# KC_BaseBoardSch.net
KiCad netlist of a schematic drawn in Altium Designer
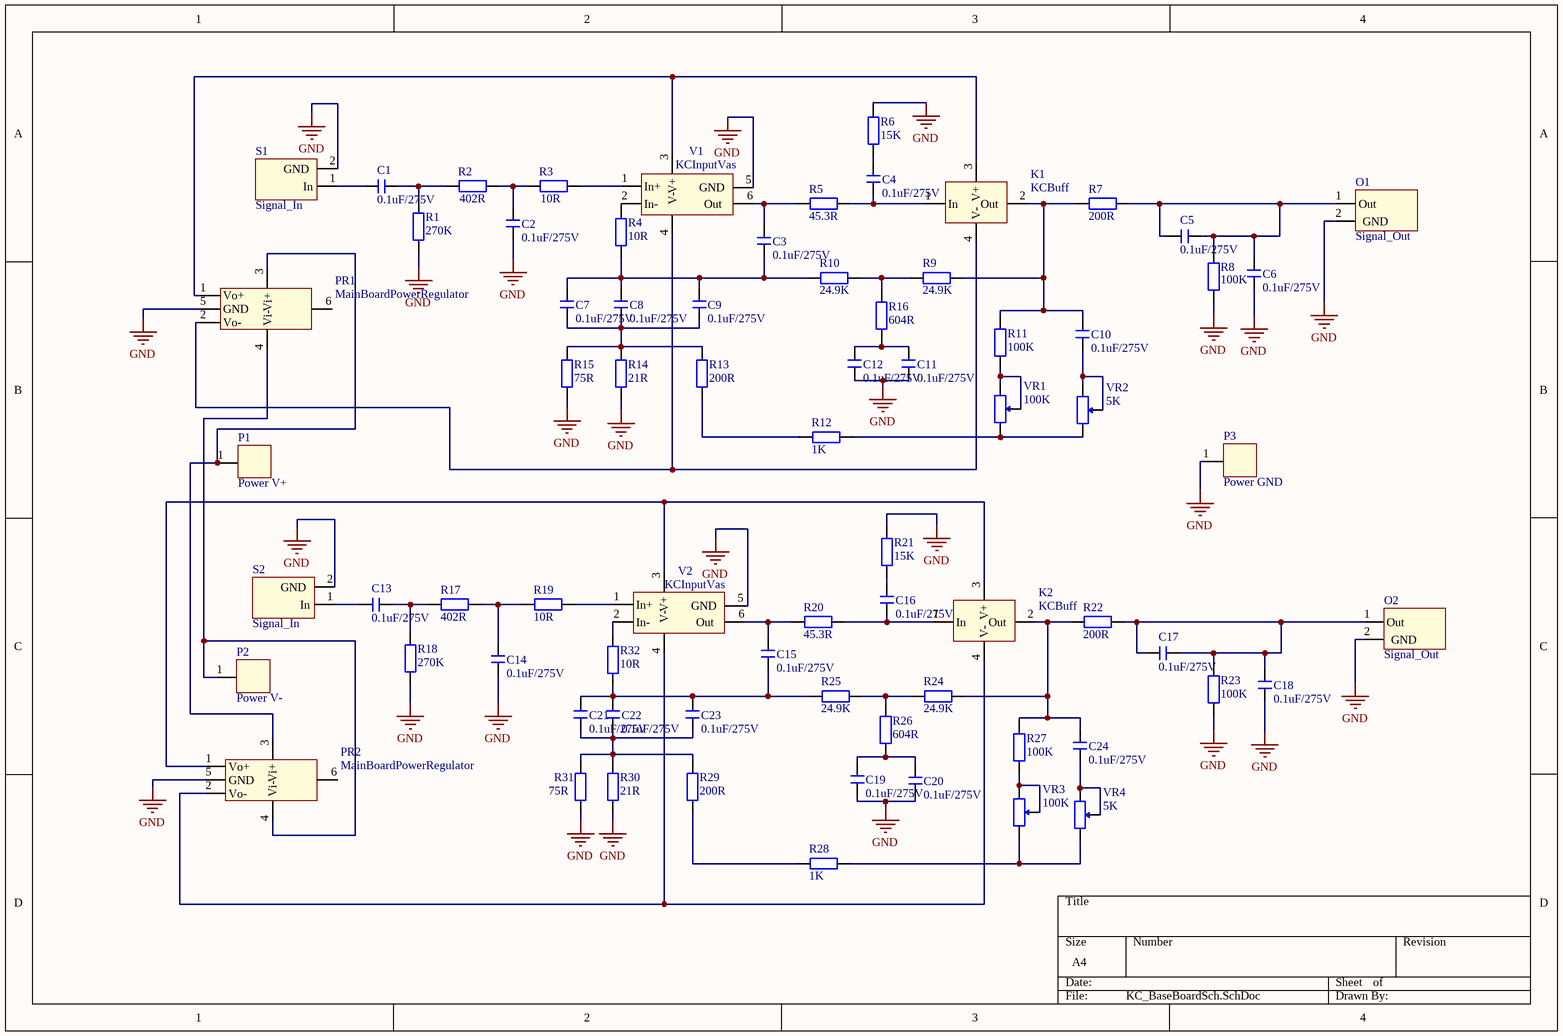
[diagram p0: KC_BaseBoardSch.SchDoc]

(export (version "E")
  (design (tool "Eeschema 10.0.6"))
  (components
    (comp (ref "C1")
      (value "0.1uF/275V")
      (footprint "CBB 50*30*30")
      (description "CBB电容")
      (fields (field (name "版权归属") "源创客"))
      (libsource (lib "电阻-电容-电感") (part "C-CBB"))
    )
    (comp (ref "C2")
      (value "0.1uF/275V")
      (footprint "CBB 6.3*6.3*5")
      (description "CBB电容")
      (fields (field (name "版权归属") "源创客"))
      (libsource (lib "电阻-电容-电感") (part "C-CBB"))
    )
    (comp (ref "C3")
      (value "0.1uF/275V")
      (footprint "CBB 6.3*6.3*5")
      (description "CBB电容")
      (fields (field (name "版权归属") "源创客"))
      (libsource (lib "电阻-电容-电感") (part "C-CBB"))
    )
    (comp (ref "C4")
      (value "0.1uF/275V")
      (footprint "CBB 6.3*6.3*5")
      (description "CBB电容")
      (fields (field (name "版权归属") "源创客"))
      (libsource (lib "电阻-电容-电感") (part "C-CBB"))
    )
    (comp (ref "C5")
      (value "0.1uF/275V")
      (footprint "CBB 6.3*6.3*5")
      (description "CBB电容")
      (fields (field (name "版权归属") "源创客"))
      (libsource (lib "电阻-电容-电感") (part "C-CBB"))
    )
    (comp (ref "C6")
      (value "0.1uF/275V")
      (footprint "CBB 6.3*6.3*5")
      (description "CBB电容")
      (fields (field (name "版权归属") "源创客"))
      (libsource (lib "电阻-电容-电感") (part "C-CBB"))
    )
    (comp (ref "C7")
      (value "0.1uF/275V")
      (footprint "CBB 6.3*6.3*5")
      (description "CBB电容")
      (fields (field (name "版权归属") "源创客"))
      (libsource (lib "电阻-电容-电感") (part "C-CBB"))
    )
    (comp (ref "C8")
      (value "0.1uF/275V")
      (footprint "CBB 6.3*6.3*5")
      (description "CBB电容")
      (fields (field (name "版权归属") "源创客"))
      (libsource (lib "电阻-电容-电感") (part "C-CBB"))
    )
    (comp (ref "C9")
      (value "0.1uF/275V")
      (footprint "CBB 6.3*6.3*5")
      (description "CBB电容")
      (fields (field (name "版权归属") "源创客"))
      (libsource (lib "电阻-电容-电感") (part "C-CBB"))
    )
    (comp (ref "C10")
      (value "0.1uF/275V")
      (footprint "CBB 10*12*8")
      (description "CBB电容")
      (fields (field (name "版权归属") "源创客"))
      (libsource (lib "电阻-电容-电感") (part "C-CBB"))
    )
    (comp (ref "C11")
      (value "0.1uF/275V")
      (footprint "CBB 6.3*6.3*5")
      (description "CBB电容")
      (fields (field (name "版权归属") "源创客"))
      (libsource (lib "电阻-电容-电感") (part "C-CBB"))
    )
    (comp (ref "C12")
      (value "0.1uF/275V")
      (footprint "CBB 6.3*6.3*5")
      (description "CBB电容")
      (fields (field (name "版权归属") "源创客"))
      (libsource (lib "电阻-电容-电感") (part "C-CBB"))
    )
    (comp (ref "C13")
      (value "0.1uF/275V")
      (footprint "CBB 50*30*30")
      (description "CBB电容")
      (fields (field (name "版权归属") "源创客"))
      (libsource (lib "电阻-电容-电感") (part "C-CBB"))
    )
    (comp (ref "C14")
      (value "0.1uF/275V")
      (footprint "CBB 6.3*6.3*5")
      (description "CBB电容")
      (fields (field (name "版权归属") "源创客"))
      (libsource (lib "电阻-电容-电感") (part "C-CBB"))
    )
    (comp (ref "C15")
      (value "0.1uF/275V")
      (footprint "CBB 6.3*6.3*5")
      (description "CBB电容")
      (fields (field (name "版权归属") "源创客"))
      (libsource (lib "电阻-电容-电感") (part "C-CBB"))
    )
    (comp (ref "C16")
      (value "0.1uF/275V")
      (footprint "CBB 6.3*6.3*5")
      (description "CBB电容")
      (fields (field (name "版权归属") "源创客"))
      (libsource (lib "电阻-电容-电感") (part "C-CBB"))
    )
    (comp (ref "C17")
      (value "0.1uF/275V")
      (footprint "CBB 6.3*6.3*5")
      (description "CBB电容")
      (fields (field (name "版权归属") "源创客"))
      (libsource (lib "电阻-电容-电感") (part "C-CBB"))
    )
    (comp (ref "C18")
      (value "0.1uF/275V")
      (footprint "CBB 6.3*6.3*5")
      (description "CBB电容")
      (fields (field (name "版权归属") "源创客"))
      (libsource (lib "电阻-电容-电感") (part "C-CBB"))
    )
    (comp (ref "C19")
      (value "0.1uF/275V")
      (footprint "CBB 6.3*6.3*5")
      (description "CBB电容")
      (fields (field (name "版权归属") "源创客"))
      (libsource (lib "电阻-电容-电感") (part "C-CBB"))
    )
    (comp (ref "C20")
      (value "0.1uF/275V")
      (footprint "CBB 6.3*6.3*5")
      (description "CBB电容")
      (fields (field (name "版权归属") "源创客"))
      (libsource (lib "电阻-电容-电感") (part "C-CBB"))
    )
    (comp (ref "C21")
      (value "0.1uF/275V")
      (footprint "CBB 6.3*6.3*5")
      (description "CBB电容")
      (fields (field (name "版权归属") "源创客"))
      (libsource (lib "电阻-电容-电感") (part "C-CBB"))
    )
    (comp (ref "C22")
      (value "0.1uF/275V")
      (footprint "CBB 6.3*6.3*5")
      (description "CBB电容")
      (fields (field (name "版权归属") "源创客"))
      (libsource (lib "电阻-电容-电感") (part "C-CBB"))
    )
    (comp (ref "C23")
      (value "0.1uF/275V")
      (footprint "CBB 6.3*6.3*5")
      (description "CBB电容")
      (fields (field (name "版权归属") "源创客"))
      (libsource (lib "电阻-电容-电感") (part "C-CBB"))
    )
    (comp (ref "C24")
      (value "0.1uF/275V")
      (footprint "CBB 10*12*8")
      (description "CBB电容")
      (fields (field (name "版权归属") "源创客"))
      (libsource (lib "电阻-电容-电感") (part "C-CBB"))
    )
    (comp (ref "K1")
      (value "KCBuff")
      (footprint "KCBuff")
      (description "King Cello Buffer Stage")
      (libsource (lib "KC_amp") (part "KCBuff"))
    )
    (comp (ref "K2")
      (value "KCBuff")
      (footprint "KCBuff")
      (description "King Cello Buffer Stage")
      (libsource (lib "KC_amp") (part "KCBuff"))
    )
    (comp (ref "O1")
      (value "Signal_Out")
      (footprint "Signal_Terminal")
      (description "Signal Out")
      (libsource (lib "KC_amp") (part "Signal_Out"))
    )
    (comp (ref "O2")
      (value "Signal_Out")
      (footprint "Signal_Terminal")
      (description "Signal Out")
      (libsource (lib "KC_amp") (part "Signal_Out"))
    )
    (comp (ref "P1")
      (value "Power V+")
      (footprint "SinglePin")
      (description "Power Pin")
      (libsource (lib "KC_amp") (part "PowerPin"))
    )
    (comp (ref "P2")
      (value "Power V-")
      (footprint "SinglePin")
      (description "Power Pin")
      (libsource (lib "KC_amp") (part "PowerPin"))
    )
    (comp (ref "P3") (value "Power GND") (footprint "SinglePin") (libsource (lib "KC_amp") (part "PowerPin")))
    (comp (ref "PR1")
      (value "MainBoardPowerRegulator")
      (footprint "KC_MBPowerReg")
      (description "King Cello Main Board Power Regulator")
      (libsource (lib "KC_amp") (part "MainBoardPowerRegulator"))
    )
    (comp (ref "PR2")
      (value "MainBoardPowerRegulator")
      (footprint "KC_MBPowerReg")
      (description "King Cello Main Board Power Regulator")
      (libsource (lib "KC_amp") (part "MainBoardPowerRegulator"))
    )
    (comp (ref "R1")
      (value "270K")
      (footprint "RS 1/2W")
      (description "直插色环电阻")
      (fields (field (name "版权归属") "源创客"))
      (libsource (lib "电阻-电容-电感") (part "R-CRR"))
    )
    (comp (ref "R2")
      (value "402R")
      (footprint "RS 1/2W")
      (description "直插色环电阻")
      (fields (field (name "版权归属") "源创客"))
      (libsource (lib "电阻-电容-电感") (part "R-CRR"))
    )
    (comp (ref "R3")
      (value "10R")
      (footprint "RS 1/2W")
      (description "直插色环电阻")
      (fields (field (name "版权归属") "源创客"))
      (libsource (lib "电阻-电容-电感") (part "R-CRR"))
    )
    (comp (ref "R4")
      (value "10R")
      (footprint "RS 1/2W")
      (description "直插色环电阻")
      (fields (field (name "版权归属") "源创客"))
      (libsource (lib "电阻-电容-电感") (part "R-CRR"))
    )
    (comp (ref "R5")
      (value "45.3R")
      (footprint "RS 1/2W")
      (description "直插色环电阻")
      (fields (field (name "版权归属") "源创客"))
      (libsource (lib "电阻-电容-电感") (part "R-CRR"))
    )
    (comp (ref "R6")
      (value "15K")
      (footprint "RS 1/2W")
      (description "直插色环电阻")
      (fields (field (name "版权归属") "源创客"))
      (libsource (lib "电阻-电容-电感") (part "R-CRR"))
    )
    (comp (ref "R7")
      (value "200R")
      (footprint "RS 1/2W")
      (description "直插色环电阻")
      (fields (field (name "版权归属") "源创客"))
      (libsource (lib "电阻-电容-电感") (part "R-CRR"))
    )
    (comp (ref "R8")
      (value "100K")
      (footprint "RS 1/2W")
      (description "直插色环电阻")
      (fields (field (name "版权归属") "源创客"))
      (libsource (lib "电阻-电容-电感") (part "R-CRR"))
    )
    (comp (ref "R9")
      (value "24.9K")
      (footprint "RS 1/2W")
      (description "直插色环电阻")
      (fields (field (name "版权归属") "源创客"))
      (libsource (lib "电阻-电容-电感") (part "R-CRR"))
    )
    (comp (ref "R10")
      (value "24.9K")
      (footprint "RS 1/2W")
      (description "直插色环电阻")
      (fields (field (name "版权归属") "源创客"))
      (libsource (lib "电阻-电容-电感") (part "R-CRR"))
    )
    (comp (ref "R11")
      (value "100K")
      (footprint "RS 1/2W")
      (description "直插色环电阻")
      (fields (field (name "版权归属") "源创客"))
      (libsource (lib "电阻-电容-电感") (part "R-CRR"))
    )
    (comp (ref "R12")
      (value "1K")
      (footprint "RS 1/2W")
      (description "直插色环电阻")
      (fields (field (name "版权归属") "源创客"))
      (libsource (lib "电阻-电容-电感") (part "R-CRR"))
    )
    (comp (ref "R13")
      (value "200R")
      (footprint "RS 1/2W")
      (description "直插色环电阻")
      (fields (field (name "版权归属") "源创客"))
      (libsource (lib "电阻-电容-电感") (part "R-CRR"))
    )
    (comp (ref "R14")
      (value "21R")
      (footprint "RS 1/2W")
      (description "直插色环电阻")
      (fields (field (name "版权归属") "源创客"))
      (libsource (lib "电阻-电容-电感") (part "R-CRR"))
    )
    (comp (ref "R15")
      (value "75R")
      (footprint "RS 1/2W")
      (description "直插色环电阻")
      (fields (field (name "版权归属") "源创客"))
      (libsource (lib "电阻-电容-电感") (part "R-CRR"))
    )
    (comp (ref "R16")
      (value "604R")
      (footprint "RS 1/2W")
      (description "直插色环电阻")
      (fields (field (name "版权归属") "源创客"))
      (libsource (lib "电阻-电容-电感") (part "R-CRR"))
    )
    (comp (ref "R17")
      (value "402R")
      (footprint "RS 1/2W")
      (description "直插色环电阻")
      (fields (field (name "版权归属") "源创客"))
      (libsource (lib "电阻-电容-电感") (part "R-CRR"))
    )
    (comp (ref "R18")
      (value "270K")
      (footprint "RS 1/2W")
      (description "直插色环电阻")
      (fields (field (name "版权归属") "源创客"))
      (libsource (lib "电阻-电容-电感") (part "R-CRR"))
    )
    (comp (ref "R19")
      (value "10R")
      (footprint "RS 1/2W")
      (description "直插色环电阻")
      (fields (field (name "版权归属") "源创客"))
      (libsource (lib "电阻-电容-电感") (part "R-CRR"))
    )
    (comp (ref "R20")
      (value "45.3R")
      (footprint "RS 1/2W")
      (description "直插色环电阻")
      (fields (field (name "版权归属") "源创客"))
      (libsource (lib "电阻-电容-电感") (part "R-CRR"))
    )
    (comp (ref "R21")
      (value "15K")
      (footprint "RS 1/2W")
      (description "直插色环电阻")
      (fields (field (name "版权归属") "源创客"))
      (libsource (lib "电阻-电容-电感") (part "R-CRR"))
    )
    (comp (ref "R22")
      (value "200R")
      (footprint "RS 1/2W")
      (description "直插色环电阻")
      (fields (field (name "版权归属") "源创客"))
      (libsource (lib "电阻-电容-电感") (part "R-CRR"))
    )
    (comp (ref "R23")
      (value "100K")
      (footprint "RS 1/2W")
      (description "直插色环电阻")
      (fields (field (name "版权归属") "源创客"))
      (libsource (lib "电阻-电容-电感") (part "R-CRR"))
    )
    (comp (ref "R24")
      (value "24.9K")
      (footprint "RS 1/2W")
      (description "直插色环电阻")
      (fields (field (name "版权归属") "源创客"))
      (libsource (lib "电阻-电容-电感") (part "R-CRR"))
    )
    (comp (ref "R25")
      (value "24.9K")
      (footprint "RS 1/2W")
      (description "直插色环电阻")
      (fields (field (name "版权归属") "源创客"))
      (libsource (lib "电阻-电容-电感") (part "R-CRR"))
    )
    (comp (ref "R26")
      (value "604R")
      (footprint "RS 1/2W")
      (description "直插色环电阻")
      (fields (field (name "版权归属") "源创客"))
      (libsource (lib "电阻-电容-电感") (part "R-CRR"))
    )
    (comp (ref "R27")
      (value "100K")
      (footprint "RS 1/2W")
      (description "直插色环电阻")
      (fields (field (name "版权归属") "源创客"))
      (libsource (lib "电阻-电容-电感") (part "R-CRR"))
    )
    (comp (ref "R28")
      (value "1K")
      (footprint "RS 1/2W")
      (description "直插色环电阻")
      (fields (field (name "版权归属") "源创客"))
      (libsource (lib "电阻-电容-电感") (part "R-CRR"))
    )
    (comp (ref "R29")
      (value "200R")
      (footprint "RS 1/2W")
      (description "直插色环电阻")
      (fields (field (name "版权归属") "源创客"))
      (libsource (lib "电阻-电容-电感") (part "R-CRR"))
    )
    (comp (ref "R30")
      (value "21R")
      (footprint "RS 1/2W")
      (description "直插色环电阻")
      (fields (field (name "版权归属") "源创客"))
      (libsource (lib "电阻-电容-电感") (part "R-CRR"))
    )
    (comp (ref "R31")
      (value "75R")
      (footprint "RS 1/2W")
      (description "直插色环电阻")
      (fields (field (name "版权归属") "源创客"))
      (libsource (lib "电阻-电容-电感") (part "R-CRR"))
    )
    (comp (ref "R32")
      (value "10R")
      (footprint "RS 1/2W")
      (description "直插色环电阻")
      (fields (field (name "版权归属") "源创客"))
      (libsource (lib "电阻-电容-电感") (part "R-CRR"))
    )
    (comp (ref "S1")
      (value "Signal_In")
      (footprint "Signal_Terminal")
      (description "Signal In")
      (libsource (lib "KC_amp") (part "Signal_In"))
    )
    (comp (ref "S2")
      (value "Signal_In")
      (footprint "Signal_Terminal")
      (description "Signal In")
      (libsource (lib "KC_amp") (part "Signal_In"))
    )
    (comp (ref "V1")
      (value "KCInputVas")
      (footprint "KCIn_VAS")
      (description "King Cello Input Stage and VAS")
      (libsource (lib "KC_amp") (part "KCInputVas"))
    )
    (comp (ref "V2")
      (value "KCInputVas")
      (footprint "KCIn_VAS")
      (description "King Cello Input Stage and VAS")
      (libsource (lib "KC_amp") (part "KCInputVas"))
    )
    (comp (ref "VR1")
      (value "100K")
      (footprint "RS 1/2W-VR")
      (description "直插可调电阻-顶调")
      (libsource (lib "电阻-电容-电感") (part "VR-W"))
    )
    (comp (ref "VR2")
      (value "5K")
      (footprint "RS 1/2W-VR")
      (description "直插可调电阻-顶调")
      (libsource (lib "电阻-电容-电感") (part "VR-W"))
    )
    (comp (ref "VR3")
      (value "100K")
      (footprint "RS 1/2W-VR")
      (description "直插可调电阻-顶调")
      (libsource (lib "电阻-电容-电感") (part "VR-W"))
    )
    (comp (ref "VR4")
      (value "5K")
      (footprint "RS 1/2W-VR")
      (description "直插可调电阻-顶调")
      (libsource (lib "电阻-电容-电感") (part "VR-W"))
    )
  )
  (nets
    (net (code "1") (name "GND") (class "Default")
      (node (ref "C11") (pin "1") (pinfunction "1_1") (pintype "passive"))
      (node (ref "C12") (pin "1") (pinfunction "1_1") (pintype "passive"))
      (node (ref "C14") (pin "1") (pinfunction "1_1") (pintype "passive"))
      (node (ref "C18") (pin "2") (pinfunction "2_2") (pintype "passive"))
      (node (ref "C19") (pin "2") (pinfunction "2_2") (pintype "passive"))
      (node (ref "C2") (pin "1") (pinfunction "1_1") (pintype "passive"))
      (node (ref "C20") (pin "2") (pinfunction "2_2") (pintype "passive"))
      (node (ref "C6") (pin "1") (pinfunction "1_1") (pintype "passive"))
      (node (ref "O1") (pin "2") (pinfunction "GND_2") (pintype "passive"))
      (node (ref "O2") (pin "2") (pinfunction "GND_2") (pintype "passive"))
      (node (ref "P3") (pin "1") (pintype "passive"))
      (node (ref "PR1") (pin "5") (pinfunction "GND_5") (pintype "passive"))
      (node (ref "PR2") (pin "5") (pinfunction "GND_5") (pintype "passive"))
      (node (ref "R1") (pin "1") (pinfunction "1_1") (pintype "passive"))
      (node (ref "R14") (pin "1") (pinfunction "1_1") (pintype "passive"))
      (node (ref "R15") (pin "1") (pinfunction "1_1") (pintype "passive"))
      (node (ref "R18") (pin "1") (pinfunction "1_1") (pintype "passive"))
      (node (ref "R21") (pin "2") (pinfunction "2_2") (pintype "passive"))
      (node (ref "R23") (pin "2") (pinfunction "2_2") (pintype "passive"))
      (node (ref "R30") (pin "1") (pinfunction "1_1") (pintype "passive"))
      (node (ref "R31") (pin "1") (pinfunction "1_1") (pintype "passive"))
      (node (ref "R6") (pin "1") (pinfunction "1_1") (pintype "passive"))
      (node (ref "R8") (pin "1") (pinfunction "1_1") (pintype "passive"))
      (node (ref "S1") (pin "2") (pinfunction "GND_2") (pintype "passive"))
      (node (ref "S2") (pin "2") (pinfunction "GND_2") (pintype "passive"))
      (node (ref "V1") (pin "5") (pinfunction "GND_5") (pintype "passive"))
      (node (ref "V2") (pin "5") (pinfunction "GND_5") (pintype "passive"))
    )
    (net (code "2") (name "Net-(C1-Pad2)") (class "Default")
      (node (ref "C1") (pin "2") (pinfunction "2_2") (pintype "passive"))
      (node (ref "R1") (pin "2") (pinfunction "2_2") (pintype "passive"))
      (node (ref "R2") (pin "1") (pinfunction "1_1") (pintype "passive"))
    )
    (net (code "3") (name "Net-(C2-Pad2)") (class "Default")
      (node (ref "C2") (pin "2") (pinfunction "2_2") (pintype "passive"))
      (node (ref "R2") (pin "2") (pinfunction "2_2") (pintype "passive"))
      (node (ref "R3") (pin "2") (pinfunction "2_2") (pintype "passive"))
    )
    (net (code "4") (name "Net-(C3-Pad1)") (class "Default")
      (node (ref "C3") (pin "1") (pinfunction "1_1") (pintype "passive"))
      (node (ref "C7") (pin "2") (pinfunction "2_2") (pintype "passive"))
      (node (ref "C8") (pin "2") (pinfunction "2_2") (pintype "passive"))
      (node (ref "C9") (pin "2") (pinfunction "2_2") (pintype "passive"))
      (node (ref "R10") (pin "2") (pinfunction "2_2") (pintype "passive"))
      (node (ref "R4") (pin "1") (pinfunction "1_1") (pintype "passive"))
    )
    (net (code "5") (name "Net-(C4-Pad2)") (class "Default")
      (node (ref "C4") (pin "2") (pinfunction "2_2") (pintype "passive"))
      (node (ref "R6") (pin "2") (pinfunction "2_2") (pintype "passive"))
    )
    (net (code "6") (name "Net-(C7-Pad1)") (class "Default")
      (node (ref "C7") (pin "1") (pinfunction "1_1") (pintype "passive"))
      (node (ref "C8") (pin "1") (pinfunction "1_1") (pintype "passive"))
      (node (ref "C9") (pin "1") (pinfunction "1_1") (pintype "passive"))
      (node (ref "R13") (pin "2") (pinfunction "2_2") (pintype "passive"))
      (node (ref "R14") (pin "2") (pinfunction "2_2") (pintype "passive"))
      (node (ref "R15") (pin "2") (pinfunction "2_2") (pintype "passive"))
    )
    (net (code "7") (name "Net-(C10-Pad1)") (class "Default")
      (node (ref "C10") (pin "1") (pinfunction "1_1") (pintype "passive"))
      (node (ref "VR2") (pin "1") (pinfunction "1_1") (pintype "passive"))
      (node (ref "VR2") (pin "3") (pinfunction "3_3") (pintype "passive"))
    )
    (net (code "8") (name "Net-(C11-Pad2)") (class "Default")
      (node (ref "C11") (pin "2") (pinfunction "2_2") (pintype "passive"))
      (node (ref "C12") (pin "2") (pinfunction "2_2") (pintype "passive"))
      (node (ref "R16") (pin "1") (pinfunction "1_1") (pintype "passive"))
    )
    (net (code "9") (name "Net-(C13-Pad2)") (class "Default")
      (node (ref "C13") (pin "2") (pinfunction "2_2") (pintype "passive"))
      (node (ref "R17") (pin "1") (pinfunction "1_1") (pintype "passive"))
      (node (ref "R18") (pin "2") (pinfunction "2_2") (pintype "passive"))
    )
    (net (code "10") (name "Net-(C14-Pad2)") (class "Default")
      (node (ref "C14") (pin "2") (pinfunction "2_2") (pintype "passive"))
      (node (ref "R17") (pin "2") (pinfunction "2_2") (pintype "passive"))
      (node (ref "R19") (pin "1") (pinfunction "1_1") (pintype "passive"))
    )
    (net (code "11") (name "Net-(C15-Pad1)") (class "Default")
      (node (ref "C15") (pin "1") (pinfunction "1_1") (pintype "passive"))
      (node (ref "C21") (pin "1") (pinfunction "1_1") (pintype "passive"))
      (node (ref "C22") (pin "1") (pinfunction "1_1") (pintype "passive"))
      (node (ref "C23") (pin "1") (pinfunction "1_1") (pintype "passive"))
      (node (ref "R25") (pin "1") (pinfunction "1_1") (pintype "passive"))
      (node (ref "R32") (pin "1") (pinfunction "1_1") (pintype "passive"))
    )
    (net (code "12") (name "Net-(C16-Pad2)") (class "Default")
      (node (ref "C16") (pin "2") (pinfunction "2_2") (pintype "passive"))
      (node (ref "R21") (pin "1") (pinfunction "1_1") (pintype "passive"))
    )
    (net (code "13") (name "Net-(C19-Pad1)") (class "Default")
      (node (ref "C19") (pin "1") (pinfunction "1_1") (pintype "passive"))
      (node (ref "C20") (pin "1") (pinfunction "1_1") (pintype "passive"))
      (node (ref "R26") (pin "1") (pinfunction "1_1") (pintype "passive"))
    )
    (net (code "14") (name "Net-(C21-Pad2)") (class "Default")
      (node (ref "C21") (pin "2") (pinfunction "2_2") (pintype "passive"))
      (node (ref "C22") (pin "2") (pinfunction "2_2") (pintype "passive"))
      (node (ref "C23") (pin "2") (pinfunction "2_2") (pintype "passive"))
      (node (ref "R29") (pin "2") (pinfunction "2_2") (pintype "passive"))
      (node (ref "R30") (pin "2") (pinfunction "2_2") (pintype "passive"))
      (node (ref "R31") (pin "2") (pinfunction "2_2") (pintype "passive"))
    )
    (net (code "15") (name "Net-(C24-Pad2)") (class "Default")
      (node (ref "C24") (pin "2") (pinfunction "2_2") (pintype "passive"))
      (node (ref "VR4") (pin "1") (pinfunction "1_1") (pintype "passive"))
      (node (ref "VR4") (pin "3") (pinfunction "3_3") (pintype "passive"))
    )
    (net (code "16") (name "Net-(K1-In)") (class "Default")
      (node (ref "C4") (pin "1") (pinfunction "1_1") (pintype "passive"))
      (node (ref "K1") (pin "1") (pinfunction "In_1") (pintype "passive"))
      (node (ref "R5") (pin "1") (pinfunction "1_1") (pintype "passive"))
    )
    (net (code "17") (name "Net-(K1-Out)") (class "Default")
      (node (ref "C10") (pin "2") (pinfunction "2_2") (pintype "passive"))
      (node (ref "K1") (pin "2") (pinfunction "Out_2") (pintype "passive"))
      (node (ref "R11") (pin "1") (pinfunction "1_1") (pintype "passive"))
      (node (ref "R7") (pin "1") (pinfunction "1_1") (pintype "passive"))
      (node (ref "R9") (pin "1") (pinfunction "1_1") (pintype "passive"))
    )
    (net (code "18") (name "Net-(K1-V+)") (class "Default")
      (node (ref "K1") (pin "3") (pinfunction "V+_3") (pintype "passive"))
      (node (ref "PR1") (pin "1") (pinfunction "Vo+_1") (pintype "passive"))
      (node (ref "V1") (pin "3") (pinfunction "V+_3") (pintype "passive"))
    )
    (net (code "19") (name "Net-(K1-V-)") (class "Default")
      (node (ref "K1") (pin "4") (pinfunction "V-_4") (pintype "passive"))
      (node (ref "PR1") (pin "2") (pinfunction "Vo-_2") (pintype "passive"))
      (node (ref "V1") (pin "4") (pinfunction "V-_4") (pintype "passive"))
    )
    (net (code "20") (name "Net-(K2-In)") (class "Default")
      (node (ref "C16") (pin "1") (pinfunction "1_1") (pintype "passive"))
      (node (ref "K2") (pin "1") (pinfunction "In_1") (pintype "passive"))
      (node (ref "R20") (pin "2") (pinfunction "2_2") (pintype "passive"))
    )
    (net (code "21") (name "Net-(K2-Out)") (class "Default")
      (node (ref "C24") (pin "1") (pinfunction "1_1") (pintype "passive"))
      (node (ref "K2") (pin "2") (pinfunction "Out_2") (pintype "passive"))
      (node (ref "R22") (pin "2") (pinfunction "2_2") (pintype "passive"))
      (node (ref "R24") (pin "2") (pinfunction "2_2") (pintype "passive"))
      (node (ref "R27") (pin "1") (pinfunction "1_1") (pintype "passive"))
    )
    (net (code "22") (name "Net-(K2-V+)") (class "Default")
      (node (ref "K2") (pin "3") (pinfunction "V+_3") (pintype "passive"))
      (node (ref "PR2") (pin "1") (pinfunction "Vo+_1") (pintype "passive"))
      (node (ref "V2") (pin "3") (pinfunction "V+_3") (pintype "passive"))
    )
    (net (code "23") (name "Net-(K2-V-)") (class "Default")
      (node (ref "K2") (pin "4") (pinfunction "V-_4") (pintype "passive"))
      (node (ref "PR2") (pin "2") (pinfunction "Vo-_2") (pintype "passive"))
      (node (ref "V2") (pin "4") (pinfunction "V-_4") (pintype "passive"))
    )
    (net (code "24") (name "Net-(O1-Out)") (class "Default")
      (node (ref "C5") (pin "1") (pinfunction "1_1") (pintype "passive"))
      (node (ref "C5") (pin "2") (pinfunction "2_2") (pintype "passive"))
      (node (ref "C6") (pin "2") (pinfunction "2_2") (pintype "passive"))
      (node (ref "O1") (pin "1") (pinfunction "Out_1") (pintype "passive"))
      (node (ref "R7") (pin "2") (pinfunction "2_2") (pintype "passive"))
      (node (ref "R8") (pin "2") (pinfunction "2_2") (pintype "passive"))
    )
    (net (code "25") (name "Net-(O2-Out)") (class "Default")
      (node (ref "C17") (pin "1") (pinfunction "1_1") (pintype "passive"))
      (node (ref "C17") (pin "2") (pinfunction "2_2") (pintype "passive"))
      (node (ref "C18") (pin "1") (pinfunction "1_1") (pintype "passive"))
      (node (ref "O2") (pin "1") (pinfunction "Out_1") (pintype "passive"))
      (node (ref "R22") (pin "1") (pinfunction "1_1") (pintype "passive"))
      (node (ref "R23") (pin "1") (pinfunction "1_1") (pintype "passive"))
    )
    (net (code "26") (name "Net-(PR1-Vi+)") (class "Default")
      (node (ref "P1") (pin "1") (pintype "passive"))
      (node (ref "PR1") (pin "3") (pinfunction "Vi+_3") (pintype "passive"))
      (node (ref "PR2") (pin "3") (pinfunction "Vi+_3") (pintype "passive"))
    )
    (net (code "27") (name "Net-(PR1-Vi-)") (class "Default")
      (node (ref "P2") (pin "1") (pintype "passive"))
      (node (ref "PR1") (pin "4") (pinfunction "Vi-_4") (pintype "passive"))
      (node (ref "PR2") (pin "4") (pinfunction "Vi-_4") (pintype "passive"))
    )
    (net (code "28") (name "Net-(R10-Pad1)") (class "Default")
      (node (ref "R10") (pin "1") (pinfunction "1_1") (pintype "passive"))
      (node (ref "R16") (pin "2") (pinfunction "2_2") (pintype "passive"))
      (node (ref "R9") (pin "2") (pinfunction "2_2") (pintype "passive"))
    )
    (net (code "29") (name "Net-(R11-Pad2)") (class "Default")
      (node (ref "R11") (pin "2") (pinfunction "2_2") (pintype "passive"))
      (node (ref "VR1") (pin "1") (pinfunction "1_1") (pintype "passive"))
      (node (ref "VR1") (pin "3") (pinfunction "3_3") (pintype "passive"))
    )
    (net (code "30") (name "Net-(R12-Pad1)") (class "Default")
      (node (ref "R12") (pin "1") (pinfunction "1_1") (pintype "passive"))
      (node (ref "R13") (pin "1") (pinfunction "1_1") (pintype "passive"))
    )
    (net (code "31") (name "Net-(R12-Pad2)") (class "Default")
      (node (ref "R12") (pin "2") (pinfunction "2_2") (pintype "passive"))
      (node (ref "VR1") (pin "2") (pinfunction "2_2") (pintype "passive"))
      (node (ref "VR2") (pin "2") (pinfunction "2_2") (pintype "passive"))
    )
    (net (code "32") (name "Net-(R24-Pad1)") (class "Default")
      (node (ref "R24") (pin "1") (pinfunction "1_1") (pintype "passive"))
      (node (ref "R25") (pin "2") (pinfunction "2_2") (pintype "passive"))
      (node (ref "R26") (pin "2") (pinfunction "2_2") (pintype "passive"))
    )
    (net (code "33") (name "Net-(R27-Pad2)") (class "Default")
      (node (ref "R27") (pin "2") (pinfunction "2_2") (pintype "passive"))
      (node (ref "VR3") (pin "1") (pinfunction "1_1") (pintype "passive"))
      (node (ref "VR3") (pin "3") (pinfunction "3_3") (pintype "passive"))
    )
    (net (code "34") (name "Net-(R28-Pad1)") (class "Default")
      (node (ref "R28") (pin "1") (pinfunction "1_1") (pintype "passive"))
      (node (ref "R29") (pin "1") (pinfunction "1_1") (pintype "passive"))
    )
    (net (code "35") (name "Net-(R28-Pad2)") (class "Default")
      (node (ref "R28") (pin "2") (pinfunction "2_2") (pintype "passive"))
      (node (ref "VR3") (pin "2") (pinfunction "2_2") (pintype "passive"))
      (node (ref "VR4") (pin "2") (pinfunction "2_2") (pintype "passive"))
    )
    (net (code "36") (name "Net-(S1-In)") (class "Default")
      (node (ref "C1") (pin "1") (pinfunction "1_1") (pintype "passive"))
      (node (ref "S1") (pin "1") (pinfunction "In_1") (pintype "passive"))
    )
    (net (code "37") (name "Net-(S2-In)") (class "Default")
      (node (ref "C13") (pin "1") (pinfunction "1_1") (pintype "passive"))
      (node (ref "S2") (pin "1") (pinfunction "In_1") (pintype "passive"))
    )
    (net (code "38") (name "Net-(V1-In+)") (class "Default")
      (node (ref "R3") (pin "1") (pinfunction "1_1") (pintype "passive"))
      (node (ref "V1") (pin "1") (pinfunction "In+_1") (pintype "passive"))
    )
    (net (code "39") (name "Net-(V1-In-)") (class "Default")
      (node (ref "R4") (pin "2") (pinfunction "2_2") (pintype "passive"))
      (node (ref "V1") (pin "2") (pinfunction "In-_2") (pintype "passive"))
    )
    (net (code "40") (name "Net-(V1-Out)") (class "Default")
      (node (ref "C3") (pin "2") (pinfunction "2_2") (pintype "passive"))
      (node (ref "R5") (pin "2") (pinfunction "2_2") (pintype "passive"))
      (node (ref "V1") (pin "6") (pinfunction "Out_6") (pintype "passive"))
    )
    (net (code "41") (name "Net-(V2-In+)") (class "Default")
      (node (ref "R19") (pin "2") (pinfunction "2_2") (pintype "passive"))
      (node (ref "V2") (pin "1") (pinfunction "In+_1") (pintype "passive"))
    )
    (net (code "42") (name "Net-(V2-In-)") (class "Default")
      (node (ref "R32") (pin "2") (pinfunction "2_2") (pintype "passive"))
      (node (ref "V2") (pin "2") (pinfunction "In-_2") (pintype "passive"))
    )
    (net (code "43") (name "Net-(V2-Out)") (class "Default")
      (node (ref "C15") (pin "2") (pinfunction "2_2") (pintype "passive"))
      (node (ref "R20") (pin "1") (pinfunction "1_1") (pintype "passive"))
      (node (ref "V2") (pin "6") (pinfunction "Out_6") (pintype "passive"))
    )
    (net (code "44") (name "unconnected-(PR1-Pad6)") (class "Default")
      (node (ref "PR1") (pin "6") (pintype "passive"))
    )
    (net (code "45") (name "unconnected-(PR2-Pad6)") (class "Default")
      (node (ref "PR2") (pin "6") (pintype "passive"))
    )
  )
)
